# TI_SCH.net
KiCad netlist of a schematic drawn in Altium Designer
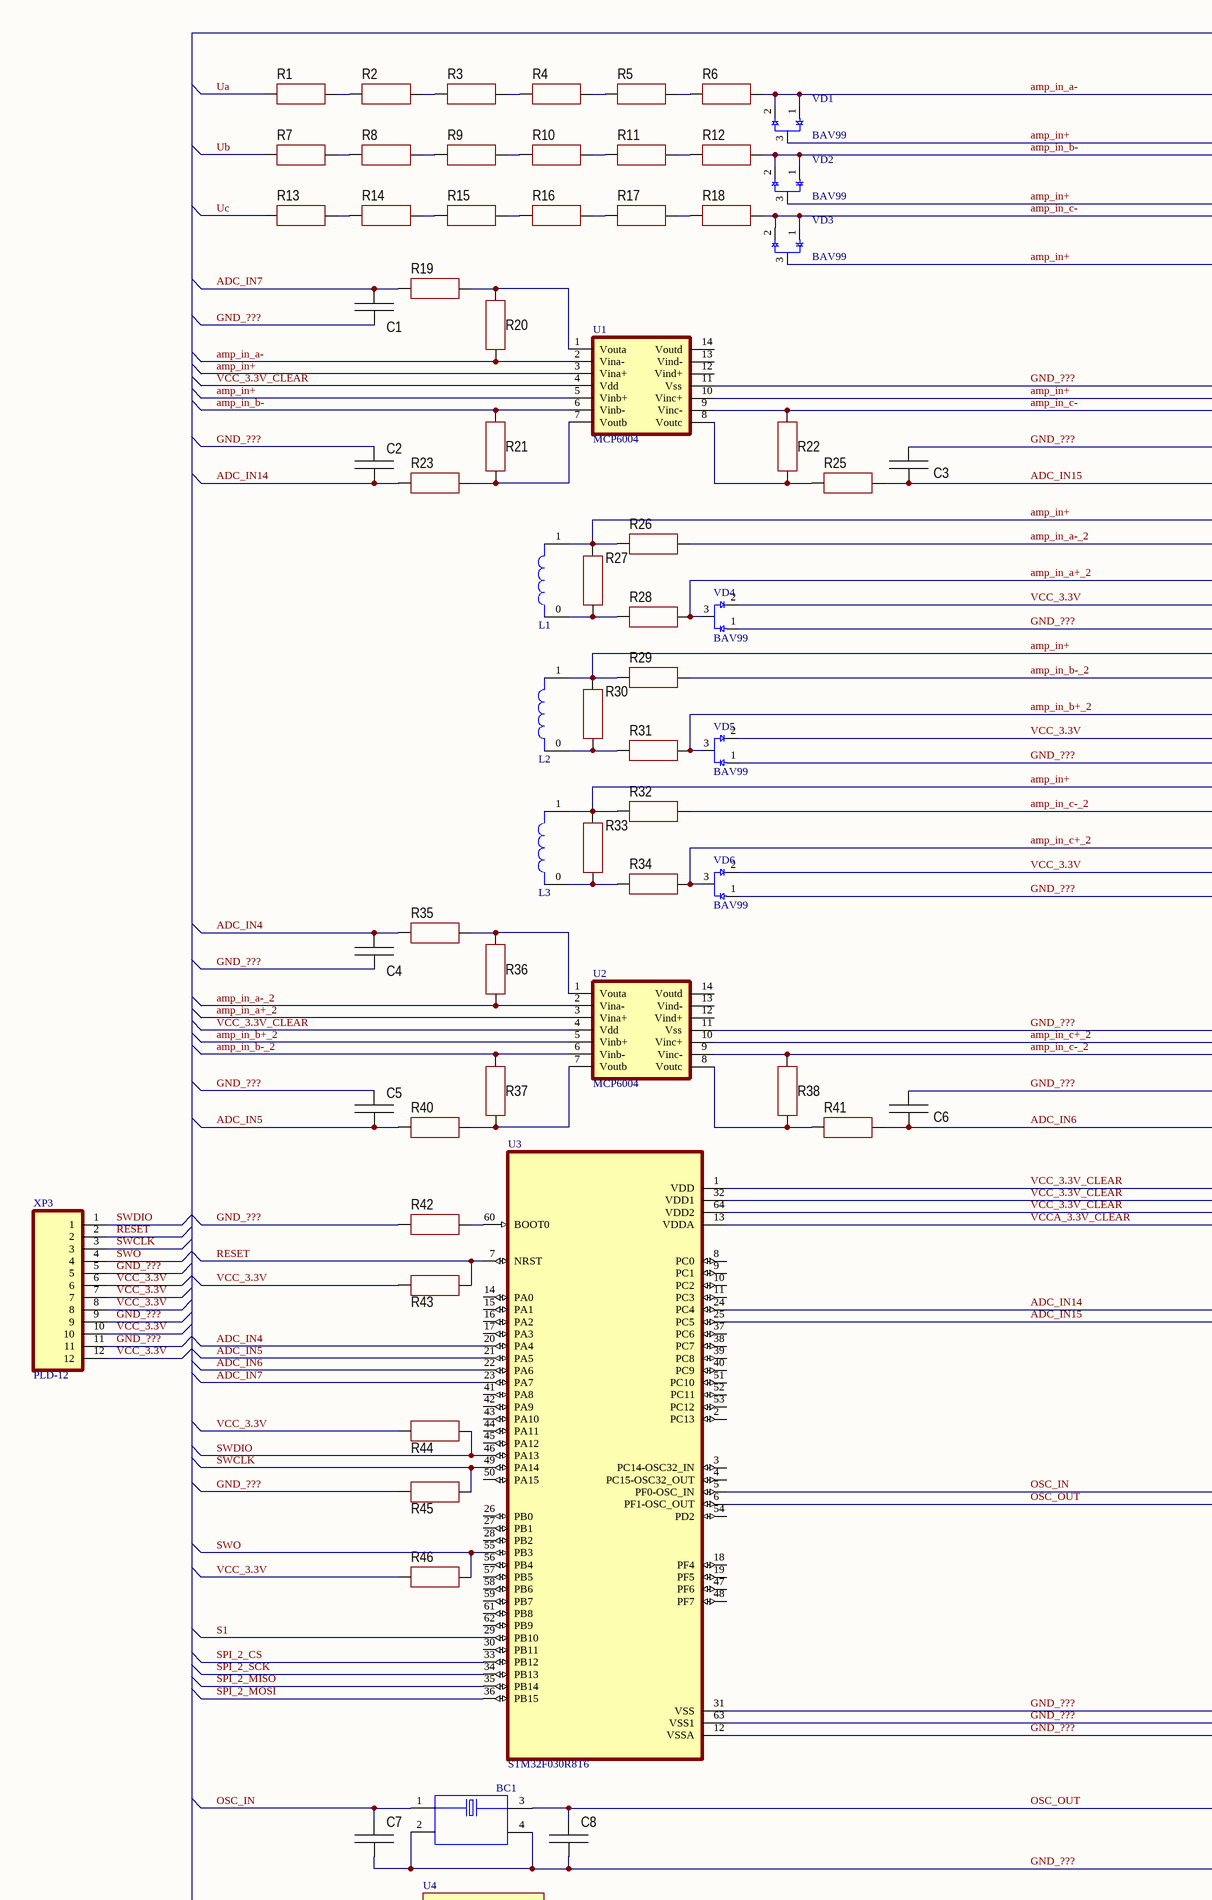
[diagram p0: TI_SCH.SchDoc, row 1 of 4 left]
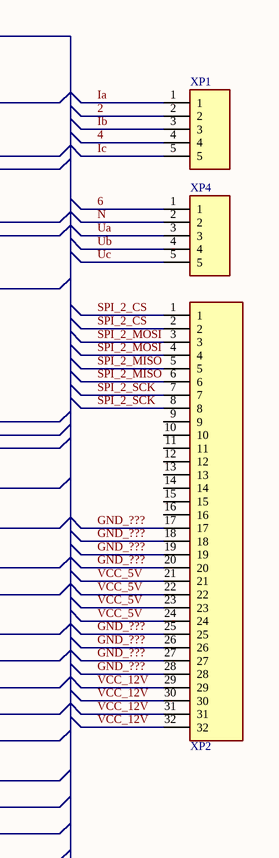
[diagram p1: TI_SCH.SchDoc, row 1 of 4 right]
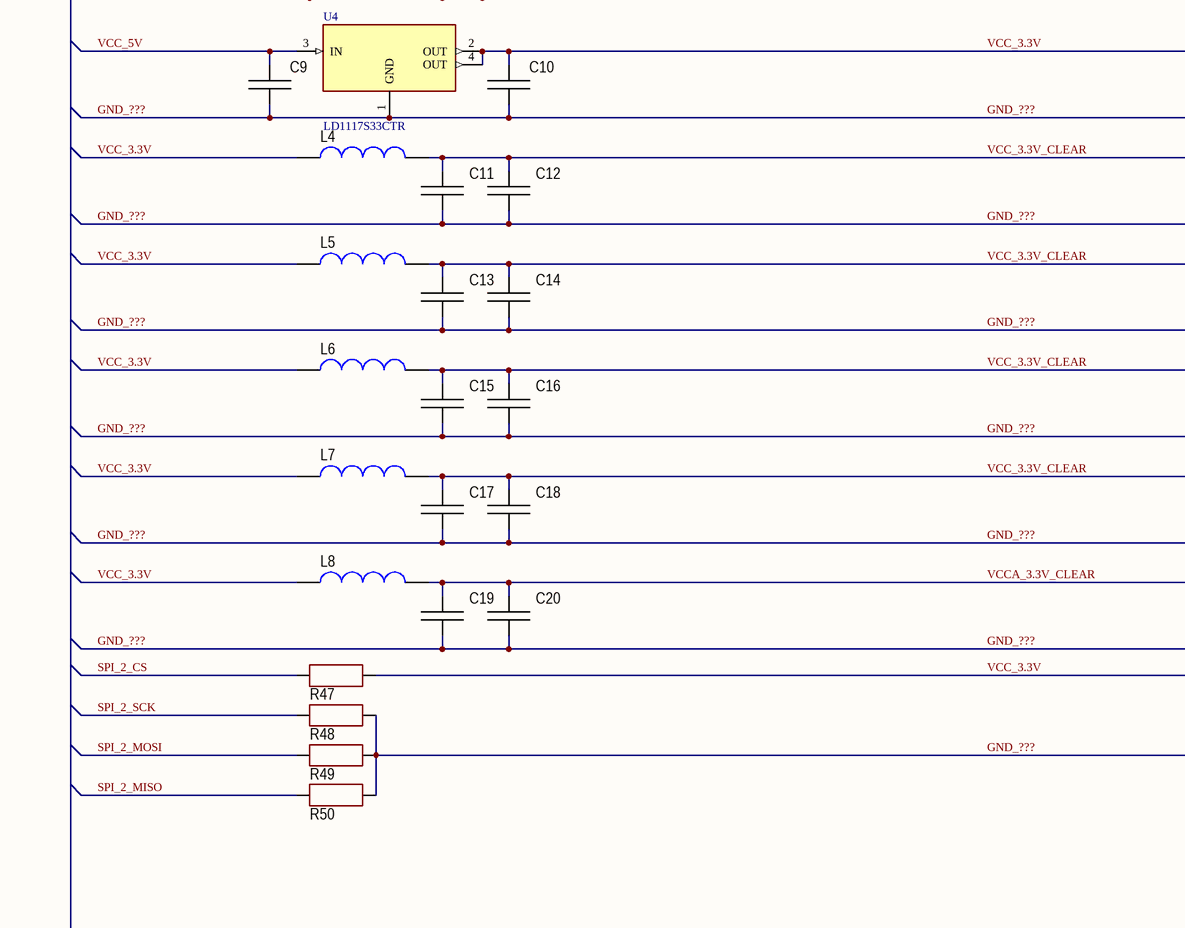
[diagram p2: TI_SCH.SchDoc, row 2 of 4 left]

(export (version "E")
  (design (tool "Eeschema 10.0.6"))
  (components
    (comp (ref "BC1")
      (value "NX2520SA-24.000000MHZ-B8")
      (footprint "XTAL_NX2520SA-24.000000MHZ-B8")
      (description "24MHz Â±10ppm Crystal 10pF 100 Ohms 4-SMD, No Lead")
      (libsource (lib "NX2520") (part "NX2520SA-24.000000MHZ-B8"))
    )
    (comp (ref "C1") (value "~") (footprint "CAP: 0603") (libsource (lib "capacitor") (part "Ceramic_0603")))
    (comp (ref "C2") (value "~") (footprint "CAP: 0603") (libsource (lib "capacitor") (part "Ceramic_0603")))
    (comp (ref "C3") (value "~") (footprint "CAP: 0603") (libsource (lib "capacitor") (part "Ceramic_0603")))
    (comp (ref "C4") (value "~") (footprint "CAP: 0603") (libsource (lib "capacitor") (part "Ceramic_0603")))
    (comp (ref "C5") (value "~") (footprint "CAP: 0603") (libsource (lib "capacitor") (part "Ceramic_0603")))
    (comp (ref "C6") (value "~") (footprint "CAP: 0603") (libsource (lib "capacitor") (part "Ceramic_0603")))
    (comp (ref "C7") (value "~") (footprint "CAP: 0603") (libsource (lib "capacitor") (part "Ceramic_0603")))
    (comp (ref "C8") (value "~") (footprint "CAP: 0603") (libsource (lib "capacitor") (part "Ceramic_0603")))
    (comp (ref "C9") (value "~") (footprint "CAP: 2220") (libsource (lib "capacitor") (part "Ceramic_2220")))
    (comp (ref "C10") (value "~") (footprint "CAP: 2220") (libsource (lib "capacitor") (part "Ceramic_2220")))
    (comp (ref "C11") (value "~") (footprint "CAP: 0603") (libsource (lib "capacitor") (part "Ceramic_0603")))
    (comp (ref "C12") (value "~") (footprint "CAP: 0603") (libsource (lib "capacitor") (part "Ceramic_0603")))
    (comp (ref "C13") (value "~") (footprint "CAP: 0603") (libsource (lib "capacitor") (part "Ceramic_0603")))
    (comp (ref "C14") (value "~") (footprint "CAP: 0603") (libsource (lib "capacitor") (part "Ceramic_0603")))
    (comp (ref "C15") (value "~") (footprint "CAP: 0603") (libsource (lib "capacitor") (part "Ceramic_0603")))
    (comp (ref "C16") (value "~") (footprint "CAP: 0603") (libsource (lib "capacitor") (part "Ceramic_0603")))
    (comp (ref "C17") (value "~") (footprint "CAP: 0603") (libsource (lib "capacitor") (part "Ceramic_0603")))
    (comp (ref "C18") (value "~") (footprint "CAP: 0603") (libsource (lib "capacitor") (part "Ceramic_0603")))
    (comp (ref "C19") (value "~") (footprint "CAP: 0603") (libsource (lib "capacitor") (part "Ceramic_0603")))
    (comp (ref "C20") (value "~") (footprint "CAP: 0603") (libsource (lib "capacitor") (part "Ceramic_0603")))
    (comp (ref "L1") (value "inductor") (footprint "inductor") (libsource (lib "inductor") (part "inductor")))
    (comp (ref "L2") (value "inductor") (footprint "inductor") (libsource (lib "inductor") (part "inductor")))
    (comp (ref "L3") (value "inductor") (footprint "inductor") (libsource (lib "inductor") (part "inductor")))
    (comp (ref "L4") (value "~") (footprint "IND: 0603") (libsource (lib "inductor") (part "Inductor_0603")))
    (comp (ref "L5") (value "~") (footprint "IND: 0603") (libsource (lib "inductor") (part "Inductor_0603")))
    (comp (ref "L6") (value "~") (footprint "IND: 0603") (libsource (lib "inductor") (part "Inductor_0603")))
    (comp (ref "L7") (value "~") (footprint "IND: 0603") (libsource (lib "inductor") (part "Inductor_0603")))
    (comp (ref "L8") (value "~") (footprint "IND: 0603") (libsource (lib "inductor") (part "Inductor_0603")))
    (comp (ref "R1") (value "~") (footprint "RES: 0603") (libsource (lib "resistor") (part "Resistor_0603")))
    (comp (ref "R2") (value "~") (footprint "RES: 0603") (libsource (lib "resistor") (part "Resistor_0603")))
    (comp (ref "R3") (value "~") (footprint "RES: 0603") (libsource (lib "resistor") (part "Resistor_0603")))
    (comp (ref "R4") (value "~") (footprint "RES: 0603") (libsource (lib "resistor") (part "Resistor_0603")))
    (comp (ref "R5") (value "~") (footprint "RES: 0603") (libsource (lib "resistor") (part "Resistor_0603")))
    (comp (ref "R6") (value "~") (footprint "RES: 0603") (libsource (lib "resistor") (part "Resistor_0603")))
    (comp (ref "R7") (value "~") (footprint "RES: 0603") (libsource (lib "resistor") (part "Resistor_0603")))
    (comp (ref "R8") (value "~") (footprint "RES: 0603") (libsource (lib "resistor") (part "Resistor_0603")))
    (comp (ref "R9") (value "~") (footprint "RES: 0603") (libsource (lib "resistor") (part "Resistor_0603")))
    (comp (ref "R10") (value "~") (footprint "RES: 0603") (libsource (lib "resistor") (part "Resistor_0603")))
    (comp (ref "R11") (value "~") (footprint "RES: 0603") (libsource (lib "resistor") (part "Resistor_0603")))
    (comp (ref "R12") (value "~") (footprint "RES: 0603") (libsource (lib "resistor") (part "Resistor_0603")))
    (comp (ref "R13") (value "~") (footprint "RES: 0603") (libsource (lib "resistor") (part "Resistor_0603")))
    (comp (ref "R14") (value "~") (footprint "RES: 0603") (libsource (lib "resistor") (part "Resistor_0603")))
    (comp (ref "R15") (value "~") (footprint "RES: 0603") (libsource (lib "resistor") (part "Resistor_0603")))
    (comp (ref "R16") (value "~") (footprint "RES: 0603") (libsource (lib "resistor") (part "Resistor_0603")))
    (comp (ref "R17") (value "~") (footprint "RES: 0603") (libsource (lib "resistor") (part "Resistor_0603")))
    (comp (ref "R18") (value "~") (footprint "RES: 0603") (libsource (lib "resistor") (part "Resistor_0603")))
    (comp (ref "R19") (value "~") (footprint "RES: 0603") (libsource (lib "resistor") (part "Resistor_0603")))
    (comp (ref "R20") (value "~") (footprint "RES: 0603") (libsource (lib "") (part "Resistor_0603_2")))
    (comp (ref "R21") (value "~") (footprint "RES: 0603") (libsource (lib "") (part "Resistor_0603_2")))
    (comp (ref "R22") (value "~") (footprint "RES: 0603") (libsource (lib "") (part "Resistor_0603_2")))
    (comp (ref "R23") (value "~") (footprint "RES: 0603") (libsource (lib "resistor") (part "Resistor_0603")))
    (comp (ref "R25") (value "~") (footprint "RES: 0603") (libsource (lib "resistor") (part "Resistor_0603")))
    (comp (ref "R26") (value "~") (footprint "RES: 0603") (libsource (lib "resistor") (part "Resistor_0603")))
    (comp (ref "R27") (value "~") (footprint "RES: 0603") (libsource (lib "") (part "Resistor_0603_2")))
    (comp (ref "R28") (value "~") (footprint "RES: 0603") (libsource (lib "resistor") (part "Resistor_0603")))
    (comp (ref "R29") (value "~") (footprint "RES: 0603") (libsource (lib "resistor") (part "Resistor_0603")))
    (comp (ref "R30") (value "~") (footprint "RES: 0603") (libsource (lib "") (part "Resistor_0603_2")))
    (comp (ref "R31") (value "~") (footprint "RES: 0603") (libsource (lib "resistor") (part "Resistor_0603")))
    (comp (ref "R32") (value "~") (footprint "RES: 0603") (libsource (lib "resistor") (part "Resistor_0603")))
    (comp (ref "R33") (value "~") (footprint "RES: 0603") (libsource (lib "") (part "Resistor_0603_2")))
    (comp (ref "R34") (value "~") (footprint "RES: 0603") (libsource (lib "resistor") (part "Resistor_0603")))
    (comp (ref "R35") (value "~") (footprint "RES: 0603") (libsource (lib "resistor") (part "Resistor_0603")))
    (comp (ref "R36") (value "~") (footprint "RES: 0603") (libsource (lib "") (part "Resistor_0603_2")))
    (comp (ref "R37") (value "~") (footprint "RES: 0603") (libsource (lib "") (part "Resistor_0603_2")))
    (comp (ref "R38") (value "~") (footprint "RES: 0603") (libsource (lib "") (part "Resistor_0603_2")))
    (comp (ref "R40") (value "~") (footprint "RES: 0603") (libsource (lib "resistor") (part "Resistor_0603")))
    (comp (ref "R41") (value "~") (footprint "RES: 0603") (libsource (lib "resistor") (part "Resistor_0603")))
    (comp (ref "R42") (value "~") (footprint "RES: 0603") (libsource (lib "resistor") (part "Resistor_0603")))
    (comp (ref "R43") (value "~") (footprint "RES: 0603") (libsource (lib "resistor") (part "Resistor_0603")))
    (comp (ref "R44") (value "~") (footprint "RES: 0603") (libsource (lib "resistor") (part "Resistor_0603")))
    (comp (ref "R45") (value "~") (footprint "RES: 0603") (libsource (lib "resistor") (part "Resistor_0603")))
    (comp (ref "R46") (value "~") (footprint "RES: 0603") (libsource (lib "") (part "Resistor_0603_1")))
    (comp (ref "R47") (value "~") (footprint "RES: 0603") (libsource (lib "") (part "Resistor_0603_1")))
    (comp (ref "R48") (value "~") (footprint "RES: 0603") (libsource (lib "") (part "Resistor_0603_1")))
    (comp (ref "R49") (value "~") (footprint "RES: 0603") (libsource (lib "") (part "Resistor_0603_1")))
    (comp (ref "R50") (value "~") (footprint "RES: 0603") (libsource (lib "") (part "Resistor_0603_1")))
    (comp (ref "U1") (value "MCP6004") (footprint "MCP6004") (libsource (lib "MCP6004") (part "MCP6004")))
    (comp (ref "U2") (value "MCP6004") (footprint "MCP6004") (libsource (lib "MCP6004") (part "MCP6004")))
    (comp (ref "U3")
      (value "STM32F030R8T6")
      (footprint "STM32F030R8T6")
      (libsource (lib "STM32F030R8T6") (part "STM32F030R8T6"))
    )
    (comp (ref "U4")
      (value "LD1117S33CTR")
      (footprint "LD1117S33CTR")
      (description "Linear Voltage Regulator IC 1 Output 800mA SOT-223")
      (libsource (lib "LD1117S33CTR") (part "LD1117S33CTR"))
    )
    (comp (ref "VD1") (value "BAV99") (footprint "BAV99") (libsource (lib "BAV99") (part "BAV99")))
    (comp (ref "VD2") (value "BAV99") (footprint "BAV99") (libsource (lib "BAV99") (part "BAV99")))
    (comp (ref "VD3") (value "BAV99") (footprint "BAV99") (libsource (lib "BAV99") (part "BAV99")))
    (comp (ref "VD4") (value "BAV99") (footprint "BAV99") (libsource (lib "BAV99") (part "BAV99")))
    (comp (ref "VD5") (value "BAV99") (footprint "BAV99") (libsource (lib "BAV99") (part "BAV99")))
    (comp (ref "VD6") (value "BAV99") (footprint "BAV99") (libsource (lib "BAV99") (part "BAV99")))
    (comp (ref "XP1")
      (value "MSTB 2.5 5-GF-5.08")
      (footprint "MSTB 2.5 5-GF-5.08")
      (libsource (lib "MSTB 2,5 5-GF-5,08") (part "MSTB 2,5 5-GF-5,08"))
    )
    (comp (ref "XP2")
      (value "DIN41612R (DS1118-32M-R23)")
      (footprint "DIN41612R (DS1118-32M-R23)")
      (libsource (lib "DIN41612R (DS1118-32M-R23)") (part "DIN41612R (DS1118-32M-R23)"))
    )
    (comp (ref "XP3") (value "PLD-12") (footprint "PLD-12") (libsource (lib "PLD-12") (part "PLD-12")))
    (comp (ref "XP4")
      (value "MSTB 2.5 5-GF-5.08")
      (footprint "MSTB 2.5 5-GF-5.08")
      (libsource (lib "MSTB 2,5 5-GF-5,08") (part "MSTB 2,5 5-GF-5,08"))
    )
  )
  (nets
    (net (code "1") (name "/2") (class "Default")
      (node (ref "XP1") (pin "2") (pinfunction "2_2") (pintype "passive"))
    )
    (net (code "2") (name "/4") (class "Default")
      (node (ref "XP1") (pin "4") (pinfunction "4_4") (pintype "passive"))
    )
    (net (code "3") (name "/6") (class "Default")
      (node (ref "XP4") (pin "1") (pinfunction "1_1") (pintype "passive"))
    )
    (net (code "4") (name "/ADC_IN4") (class "Default")
      (node (ref "C4") (pin "1") (pinfunction "1_1") (pintype "passive"))
      (node (ref "R35") (pin "1") (pinfunction "1_1") (pintype "passive"))
      (node (ref "U3") (pin "20") (pinfunction "PA4_20") (pintype "bidirectional"))
    )
    (net (code "5") (name "/ADC_IN5") (class "Default")
      (node (ref "C5") (pin "1") (pinfunction "1_1") (pintype "passive"))
      (node (ref "R40") (pin "1") (pinfunction "1_1") (pintype "passive"))
      (node (ref "U3") (pin "21") (pinfunction "PA5_21") (pintype "bidirectional"))
    )
    (net (code "6") (name "/ADC_IN6") (class "Default")
      (node (ref "C6") (pin "1") (pinfunction "1_1") (pintype "passive"))
      (node (ref "R41") (pin "2") (pinfunction "2_2") (pintype "passive"))
      (node (ref "U3") (pin "22") (pinfunction "PA6_22") (pintype "bidirectional"))
    )
    (net (code "7") (name "/ADC_IN7") (class "Default")
      (node (ref "C1") (pin "1") (pinfunction "1_1") (pintype "passive"))
      (node (ref "R19") (pin "1") (pinfunction "1_1") (pintype "passive"))
      (node (ref "U3") (pin "23") (pinfunction "PA7_23") (pintype "bidirectional"))
    )
    (net (code "8") (name "/ADC_IN14") (class "Default")
      (node (ref "C2") (pin "1") (pinfunction "1_1") (pintype "passive"))
      (node (ref "R23") (pin "1") (pinfunction "1_1") (pintype "passive"))
      (node (ref "U3") (pin "24") (pinfunction "PC4_24") (pintype "bidirectional"))
    )
    (net (code "9") (name "/ADC_IN15") (class "Default")
      (node (ref "C3") (pin "1") (pinfunction "1_1") (pintype "passive"))
      (node (ref "R25") (pin "2") (pinfunction "2_2") (pintype "passive"))
      (node (ref "U3") (pin "25") (pinfunction "PC5_25") (pintype "bidirectional"))
    )
    (net (code "10") (name "/GND_???") (class "Default")
      (node (ref "BC1") (pin "2") (pinfunction "2_2") (pintype "passive"))
      (node (ref "BC1") (pin "4") (pinfunction "4_4") (pintype "passive"))
      (node (ref "C1") (pin "2") (pinfunction "2_2") (pintype "passive"))
      (node (ref "C10") (pin "1") (pinfunction "1_1") (pintype "passive"))
      (node (ref "C11") (pin "1") (pinfunction "1_1") (pintype "passive"))
      (node (ref "C12") (pin "1") (pinfunction "1_1") (pintype "passive"))
      (node (ref "C13") (pin "1") (pinfunction "1_1") (pintype "passive"))
      (node (ref "C14") (pin "1") (pinfunction "1_1") (pintype "passive"))
      (node (ref "C15") (pin "1") (pinfunction "1_1") (pintype "passive"))
      (node (ref "C16") (pin "1") (pinfunction "1_1") (pintype "passive"))
      (node (ref "C17") (pin "1") (pinfunction "1_1") (pintype "passive"))
      (node (ref "C18") (pin "1") (pinfunction "1_1") (pintype "passive"))
      (node (ref "C19") (pin "1") (pinfunction "1_1") (pintype "passive"))
      (node (ref "C2") (pin "2") (pinfunction "2_2") (pintype "passive"))
      (node (ref "C20") (pin "1") (pinfunction "1_1") (pintype "passive"))
      (node (ref "C3") (pin "2") (pinfunction "2_2") (pintype "passive"))
      (node (ref "C4") (pin "2") (pinfunction "2_2") (pintype "passive"))
      (node (ref "C5") (pin "2") (pinfunction "2_2") (pintype "passive"))
      (node (ref "C6") (pin "2") (pinfunction "2_2") (pintype "passive"))
      (node (ref "C7") (pin "2") (pinfunction "2_2") (pintype "passive"))
      (node (ref "C8") (pin "2") (pinfunction "2_2") (pintype "passive"))
      (node (ref "C9") (pin "1") (pinfunction "1_1") (pintype "passive"))
      (node (ref "R42") (pin "1") (pinfunction "1_1") (pintype "passive"))
      (node (ref "R45") (pin "1") (pinfunction "1_1") (pintype "passive"))
      (node (ref "R48") (pin "1") (pinfunction "1_1") (pintype "passive"))
      (node (ref "R49") (pin "1") (pinfunction "1_1") (pintype "passive"))
      (node (ref "R50") (pin "1") (pinfunction "1_1") (pintype "passive"))
      (node (ref "U1") (pin "11") (pinfunction "Vss_11") (pintype "power_in"))
      (node (ref "U2") (pin "11") (pinfunction "Vss_11") (pintype "power_in"))
      (node (ref "U3") (pin "12") (pinfunction "VSSA_12") (pintype "power_in"))
      (node (ref "U3") (pin "31") (pinfunction "VSS_31") (pintype "power_in"))
      (node (ref "U3") (pin "63") (pinfunction "VSS1_63") (pintype "power_in"))
      (node (ref "U4") (pin "1") (pinfunction "GND_1") (pintype "passive"))
      (node (ref "VD4") (pin "1") (pinfunction "G_1") (pintype "passive"))
      (node (ref "VD5") (pin "1") (pinfunction "G_1") (pintype "passive"))
      (node (ref "VD6") (pin "1") (pinfunction "G_1") (pintype "passive"))
      (node (ref "XP2") (pin "17") (pinfunction "17_17") (pintype "passive"))
      (node (ref "XP2") (pin "18") (pinfunction "18_18") (pintype "passive"))
      (node (ref "XP2") (pin "19") (pinfunction "19_19") (pintype "passive"))
      (node (ref "XP2") (pin "20") (pinfunction "20_20") (pintype "passive"))
      (node (ref "XP2") (pin "25") (pinfunction "25_25") (pintype "passive"))
      (node (ref "XP2") (pin "26") (pinfunction "26_26") (pintype "passive"))
      (node (ref "XP2") (pin "27") (pinfunction "27_27") (pintype "passive"))
      (node (ref "XP2") (pin "28") (pinfunction "28_28") (pintype "passive"))
      (node (ref "XP3") (pin "11") (pinfunction "11_11") (pintype "passive"))
      (node (ref "XP3") (pin "5") (pinfunction "5_5") (pintype "passive"))
      (node (ref "XP3") (pin "9") (pinfunction "9_9") (pintype "passive"))
    )
    (net (code "11") (name "/Ia") (class "Default")
      (node (ref "XP1") (pin "1") (pinfunction "1_1") (pintype "passive"))
    )
    (net (code "12") (name "/Ib") (class "Default")
      (node (ref "XP1") (pin "3") (pinfunction "3_3") (pintype "passive"))
    )
    (net (code "13") (name "/Ic") (class "Default")
      (node (ref "XP1") (pin "5") (pinfunction "5_5") (pintype "passive"))
    )
    (net (code "14") (name "/N") (class "Default")
      (node (ref "XP4") (pin "2") (pinfunction "2_2") (pintype "passive"))
    )
    (net (code "15") (name "/OSC_IN") (class "Default")
      (node (ref "BC1") (pin "1") (pinfunction "1_1") (pintype "passive"))
      (node (ref "C7") (pin "1") (pinfunction "1_1") (pintype "passive"))
      (node (ref "U3") (pin "5") (pinfunction "PF0-OSC_IN_5") (pintype "bidirectional"))
    )
    (net (code "16") (name "/OSC_OUT") (class "Default")
      (node (ref "BC1") (pin "3") (pinfunction "3_3") (pintype "passive"))
      (node (ref "C8") (pin "1") (pinfunction "1_1") (pintype "passive"))
      (node (ref "U3") (pin "6") (pinfunction "PF1-OSC_OUT_6") (pintype "bidirectional"))
    )
    (net (code "17") (name "/RESET") (class "Default")
      (node (ref "R43") (pin "2") (pinfunction "2_2") (pintype "passive"))
      (node (ref "U3") (pin "7") (pinfunction "NRST_7") (pintype "bidirectional"))
      (node (ref "XP3") (pin "2") (pinfunction "2_2") (pintype "passive"))
    )
    (net (code "18") (name "/S1") (class "Default")
      (node (ref "U3") (pin "29") (pinfunction "PB10_29") (pintype "bidirectional"))
    )
    (net (code "19") (name "/SPI_2_CS") (class "Default")
      (node (ref "R47") (pin "2") (pinfunction "2_2") (pintype "passive"))
      (node (ref "U3") (pin "33") (pinfunction "PB12_33") (pintype "bidirectional"))
      (node (ref "XP2") (pin "1") (pinfunction "1_1") (pintype "passive"))
      (node (ref "XP2") (pin "2") (pinfunction "2_2") (pintype "passive"))
    )
    (net (code "20") (name "/SPI_2_MISO") (class "Default")
      (node (ref "R50") (pin "2") (pinfunction "2_2") (pintype "passive"))
      (node (ref "U3") (pin "35") (pinfunction "PB14_35") (pintype "bidirectional"))
      (node (ref "XP2") (pin "5") (pinfunction "5_5") (pintype "passive"))
      (node (ref "XP2") (pin "6") (pinfunction "6_6") (pintype "passive"))
    )
    (net (code "21") (name "/SPI_2_MOSI") (class "Default")
      (node (ref "R49") (pin "2") (pinfunction "2_2") (pintype "passive"))
      (node (ref "U3") (pin "36") (pinfunction "PB15_36") (pintype "bidirectional"))
      (node (ref "XP2") (pin "3") (pinfunction "3_3") (pintype "passive"))
      (node (ref "XP2") (pin "4") (pinfunction "4_4") (pintype "passive"))
    )
    (net (code "22") (name "/SPI_2_SCK") (class "Default")
      (node (ref "R48") (pin "2") (pinfunction "2_2") (pintype "passive"))
      (node (ref "U3") (pin "34") (pinfunction "PB13_34") (pintype "bidirectional"))
      (node (ref "XP2") (pin "7") (pinfunction "7_7") (pintype "passive"))
      (node (ref "XP2") (pin "8") (pinfunction "8_8") (pintype "passive"))
    )
    (net (code "23") (name "/SWCLK") (class "Default")
      (node (ref "R45") (pin "2") (pinfunction "2_2") (pintype "passive"))
      (node (ref "U3") (pin "49") (pinfunction "PA14_49") (pintype "bidirectional"))
      (node (ref "XP3") (pin "3") (pinfunction "3_3") (pintype "passive"))
    )
    (net (code "24") (name "/SWDIO") (class "Default")
      (node (ref "R44") (pin "2") (pinfunction "2_2") (pintype "passive"))
      (node (ref "U3") (pin "46") (pinfunction "PA13_46") (pintype "bidirectional"))
      (node (ref "XP3") (pin "1") (pinfunction "1_1") (pintype "passive"))
    )
    (net (code "25") (name "/SWO") (class "Default")
      (node (ref "R46") (pin "1") (pinfunction "1_1") (pintype "passive"))
      (node (ref "U3") (pin "55") (pinfunction "PB3_55") (pintype "bidirectional"))
      (node (ref "XP3") (pin "4") (pinfunction "4_4") (pintype "passive"))
    )
    (net (code "26") (name "/Ua") (class "Default")
      (node (ref "R1") (pin "1") (pinfunction "1_1") (pintype "passive"))
      (node (ref "XP4") (pin "3") (pinfunction "3_3") (pintype "passive"))
    )
    (net (code "27") (name "/Ub") (class "Default")
      (node (ref "R7") (pin "1") (pinfunction "1_1") (pintype "passive"))
      (node (ref "XP4") (pin "4") (pinfunction "4_4") (pintype "passive"))
    )
    (net (code "28") (name "/Uc") (class "Default")
      (node (ref "R13") (pin "1") (pinfunction "1_1") (pintype "passive"))
      (node (ref "XP4") (pin "5") (pinfunction "5_5") (pintype "passive"))
    )
    (net (code "29") (name "/VCCA_3.3V_CLEAR") (class "Default")
      (node (ref "C19") (pin "2") (pinfunction "2_2") (pintype "passive"))
      (node (ref "C20") (pin "2") (pinfunction "2_2") (pintype "passive"))
      (node (ref "L8") (pin "1") (pinfunction "1_1") (pintype "passive"))
      (node (ref "U3") (pin "13") (pinfunction "VDDA_13") (pintype "power_in"))
    )
    (net (code "30") (name "/VCC_3.3V") (class "Default")
      (node (ref "C10") (pin "2") (pinfunction "2_2") (pintype "passive"))
      (node (ref "L4") (pin "2") (pinfunction "2_2") (pintype "passive"))
      (node (ref "L5") (pin "2") (pinfunction "2_2") (pintype "passive"))
      (node (ref "L6") (pin "2") (pinfunction "2_2") (pintype "passive"))
      (node (ref "L7") (pin "2") (pinfunction "2_2") (pintype "passive"))
      (node (ref "L8") (pin "2") (pinfunction "2_2") (pintype "passive"))
      (node (ref "R43") (pin "1") (pinfunction "1_1") (pintype "passive"))
      (node (ref "R44") (pin "1") (pinfunction "1_1") (pintype "passive"))
      (node (ref "R46") (pin "2") (pinfunction "2_2") (pintype "passive"))
      (node (ref "R47") (pin "1") (pinfunction "1_1") (pintype "passive"))
      (node (ref "U4") (pin "2") (pinfunction "OUT_2") (pintype "output"))
      (node (ref "U4") (pin "4") (pinfunction "OUT_4") (pintype "output"))
      (node (ref "VD4") (pin "2") (pinfunction "S_2") (pintype "passive"))
      (node (ref "VD5") (pin "2") (pinfunction "S_2") (pintype "passive"))
      (node (ref "VD6") (pin "2") (pinfunction "S_2") (pintype "passive"))
      (node (ref "XP3") (pin "10") (pinfunction "10_10") (pintype "passive"))
      (node (ref "XP3") (pin "12") (pinfunction "12_12") (pintype "passive"))
      (node (ref "XP3") (pin "6") (pinfunction "6_6") (pintype "passive"))
      (node (ref "XP3") (pin "7") (pinfunction "7_7") (pintype "passive"))
      (node (ref "XP3") (pin "8") (pinfunction "8_8") (pintype "passive"))
    )
    (net (code "31") (name "/VCC_3.3V_CLEAR") (class "Default")
      (node (ref "C11") (pin "2") (pinfunction "2_2") (pintype "passive"))
      (node (ref "C12") (pin "2") (pinfunction "2_2") (pintype "passive"))
      (node (ref "C13") (pin "2") (pinfunction "2_2") (pintype "passive"))
      (node (ref "C14") (pin "2") (pinfunction "2_2") (pintype "passive"))
      (node (ref "C15") (pin "2") (pinfunction "2_2") (pintype "passive"))
      (node (ref "C16") (pin "2") (pinfunction "2_2") (pintype "passive"))
      (node (ref "C17") (pin "2") (pinfunction "2_2") (pintype "passive"))
      (node (ref "C18") (pin "2") (pinfunction "2_2") (pintype "passive"))
      (node (ref "L4") (pin "1") (pinfunction "1_1") (pintype "passive"))
      (node (ref "L5") (pin "1") (pinfunction "1_1") (pintype "passive"))
      (node (ref "L6") (pin "1") (pinfunction "1_1") (pintype "passive"))
      (node (ref "L7") (pin "1") (pinfunction "1_1") (pintype "passive"))
      (node (ref "U1") (pin "4") (pinfunction "Vdd_4") (pintype "power_in"))
      (node (ref "U2") (pin "4") (pinfunction "Vdd_4") (pintype "power_in"))
      (node (ref "U3") (pin "1") (pinfunction "VDD_1") (pintype "power_in"))
      (node (ref "U3") (pin "32") (pinfunction "VDD1_32") (pintype "power_in"))
      (node (ref "U3") (pin "64") (pinfunction "VDD2_64") (pintype "power_in"))
    )
    (net (code "32") (name "/VCC_5V") (class "Default")
      (node (ref "C9") (pin "2") (pinfunction "2_2") (pintype "passive"))
      (node (ref "U4") (pin "3") (pinfunction "IN_3") (pintype "input"))
      (node (ref "XP2") (pin "21") (pinfunction "21_21") (pintype "passive"))
      (node (ref "XP2") (pin "22") (pinfunction "22_22") (pintype "passive"))
      (node (ref "XP2") (pin "23") (pinfunction "23_23") (pintype "passive"))
      (node (ref "XP2") (pin "24") (pinfunction "24_24") (pintype "passive"))
    )
    (net (code "33") (name "/VCC_12V") (class "Default")
      (node (ref "XP2") (pin "29") (pinfunction "29_29") (pintype "passive"))
      (node (ref "XP2") (pin "30") (pinfunction "30_30") (pintype "passive"))
      (node (ref "XP2") (pin "31") (pinfunction "31_31") (pintype "passive"))
      (node (ref "XP2") (pin "32") (pinfunction "32_32") (pintype "passive"))
    )
    (net (code "34") (name "/amp_in+") (class "Default")
      (node (ref "L1") (pin "1") (pinfunction "1_1") (pintype "power_in"))
      (node (ref "L2") (pin "1") (pinfunction "1_1") (pintype "power_in"))
      (node (ref "L3") (pin "1") (pinfunction "1_1") (pintype "power_in"))
      (node (ref "R26") (pin "1") (pinfunction "1_1") (pintype "passive"))
      (node (ref "R27") (pin "2") (pinfunction "2_2") (pintype "passive"))
      (node (ref "R29") (pin "1") (pinfunction "1_1") (pintype "passive"))
      (node (ref "R30") (pin "2") (pinfunction "2_2") (pintype "passive"))
      (node (ref "R32") (pin "1") (pinfunction "1_1") (pintype "passive"))
      (node (ref "R33") (pin "2") (pinfunction "2_2") (pintype "passive"))
      (node (ref "U1") (pin "10") (pinfunction "Vinc+_10") (pintype "power_in"))
      (node (ref "U1") (pin "3") (pinfunction "Vina+_3") (pintype "power_in"))
      (node (ref "U1") (pin "5") (pinfunction "Vinb+_5") (pintype "power_in"))
      (node (ref "VD1") (pin "3") (pinfunction "D_3") (pintype "passive"))
      (node (ref "VD2") (pin "3") (pinfunction "D_3") (pintype "passive"))
      (node (ref "VD3") (pin "3") (pinfunction "D_3") (pintype "passive"))
    )
    (net (code "35") (name "/amp_in_a+_2") (class "Default")
      (node (ref "R28") (pin "2") (pinfunction "2_2") (pintype "passive"))
      (node (ref "U2") (pin "3") (pinfunction "Vina+_3") (pintype "power_in"))
      (node (ref "VD4") (pin "3") (pinfunction "D_3") (pintype "passive"))
    )
    (net (code "36") (name "/amp_in_a-") (class "Default")
      (node (ref "R20") (pin "1") (pinfunction "1_1") (pintype "passive"))
      (node (ref "R6") (pin "2") (pinfunction "2_2") (pintype "passive"))
      (node (ref "U1") (pin "2") (pinfunction "Vina-_2") (pintype "power_in"))
      (node (ref "VD1") (pin "1") (pinfunction "G_1") (pintype "passive"))
      (node (ref "VD1") (pin "2") (pinfunction "S_2") (pintype "passive"))
    )
    (net (code "37") (name "/amp_in_a-_2") (class "Default")
      (node (ref "R26") (pin "2") (pinfunction "2_2") (pintype "passive"))
      (node (ref "R36") (pin "1") (pinfunction "1_1") (pintype "passive"))
      (node (ref "U2") (pin "2") (pinfunction "Vina-_2") (pintype "power_in"))
    )
    (net (code "38") (name "/amp_in_b+_2") (class "Default")
      (node (ref "R31") (pin "2") (pinfunction "2_2") (pintype "passive"))
      (node (ref "U2") (pin "5") (pinfunction "Vinb+_5") (pintype "power_in"))
      (node (ref "VD5") (pin "3") (pinfunction "D_3") (pintype "passive"))
    )
    (net (code "39") (name "/amp_in_b-") (class "Default")
      (node (ref "R12") (pin "2") (pinfunction "2_2") (pintype "passive"))
      (node (ref "R21") (pin "2") (pinfunction "2_2") (pintype "passive"))
      (node (ref "U1") (pin "6") (pinfunction "Vinb-_6") (pintype "power_in"))
      (node (ref "VD2") (pin "1") (pinfunction "G_1") (pintype "passive"))
      (node (ref "VD2") (pin "2") (pinfunction "S_2") (pintype "passive"))
    )
    (net (code "40") (name "/amp_in_b-_2") (class "Default")
      (node (ref "R29") (pin "2") (pinfunction "2_2") (pintype "passive"))
      (node (ref "R37") (pin "2") (pinfunction "2_2") (pintype "passive"))
      (node (ref "U2") (pin "6") (pinfunction "Vinb-_6") (pintype "power_in"))
    )
    (net (code "41") (name "/amp_in_c+_2") (class "Default")
      (node (ref "R34") (pin "2") (pinfunction "2_2") (pintype "passive"))
      (node (ref "U2") (pin "10") (pinfunction "Vinc+_10") (pintype "power_in"))
      (node (ref "VD6") (pin "3") (pinfunction "D_3") (pintype "passive"))
    )
    (net (code "42") (name "/amp_in_c-") (class "Default")
      (node (ref "R18") (pin "2") (pinfunction "2_2") (pintype "passive"))
      (node (ref "R22") (pin "2") (pinfunction "2_2") (pintype "passive"))
      (node (ref "U1") (pin "9") (pinfunction "Vinc-_9") (pintype "power_in"))
      (node (ref "VD3") (pin "1") (pinfunction "G_1") (pintype "passive"))
      (node (ref "VD3") (pin "2") (pinfunction "S_2") (pintype "passive"))
    )
    (net (code "43") (name "/amp_in_c-_2") (class "Default")
      (node (ref "R32") (pin "2") (pinfunction "2_2") (pintype "passive"))
      (node (ref "R38") (pin "2") (pinfunction "2_2") (pintype "passive"))
      (node (ref "U2") (pin "9") (pinfunction "Vinc-_9") (pintype "power_in"))
    )
    (net (code "44") (name "Net-(L1-Pad0)") (class "Default")
      (node (ref "L1") (pin "0") (pinfunction "0_0") (pintype "power_in"))
      (node (ref "R27") (pin "1") (pinfunction "1_1") (pintype "passive"))
      (node (ref "R28") (pin "1") (pinfunction "1_1") (pintype "passive"))
    )
    (net (code "45") (name "Net-(L2-Pad0)") (class "Default")
      (node (ref "L2") (pin "0") (pinfunction "0_0") (pintype "power_in"))
      (node (ref "R30") (pin "1") (pinfunction "1_1") (pintype "passive"))
      (node (ref "R31") (pin "1") (pinfunction "1_1") (pintype "passive"))
    )
    (net (code "46") (name "Net-(L3-Pad0)") (class "Default")
      (node (ref "L3") (pin "0") (pinfunction "0_0") (pintype "power_in"))
      (node (ref "R33") (pin "1") (pinfunction "1_1") (pintype "passive"))
      (node (ref "R34") (pin "1") (pinfunction "1_1") (pintype "passive"))
    )
    (net (code "47") (name "Net-(R1-Pad2)") (class "Default")
      (node (ref "R1") (pin "2") (pinfunction "2_2") (pintype "passive"))
      (node (ref "R2") (pin "1") (pinfunction "1_1") (pintype "passive"))
    )
    (net (code "48") (name "Net-(R2-Pad2)") (class "Default")
      (node (ref "R2") (pin "2") (pinfunction "2_2") (pintype "passive"))
      (node (ref "R3") (pin "1") (pinfunction "1_1") (pintype "passive"))
    )
    (net (code "49") (name "Net-(R3-Pad2)") (class "Default")
      (node (ref "R3") (pin "2") (pinfunction "2_2") (pintype "passive"))
      (node (ref "R4") (pin "1") (pinfunction "1_1") (pintype "passive"))
    )
    (net (code "50") (name "Net-(R4-Pad2)") (class "Default")
      (node (ref "R4") (pin "2") (pinfunction "2_2") (pintype "passive"))
      (node (ref "R5") (pin "1") (pinfunction "1_1") (pintype "passive"))
    )
    (net (code "51") (name "Net-(R5-Pad2)") (class "Default")
      (node (ref "R5") (pin "2") (pinfunction "2_2") (pintype "passive"))
      (node (ref "R6") (pin "1") (pinfunction "1_1") (pintype "passive"))
    )
    (net (code "52") (name "Net-(R7-Pad2)") (class "Default")
      (node (ref "R7") (pin "2") (pinfunction "2_2") (pintype "passive"))
      (node (ref "R8") (pin "1") (pinfunction "1_1") (pintype "passive"))
    )
    (net (code "53") (name "Net-(R8-Pad2)") (class "Default")
      (node (ref "R8") (pin "2") (pinfunction "2_2") (pintype "passive"))
      (node (ref "R9") (pin "1") (pinfunction "1_1") (pintype "passive"))
    )
    (net (code "54") (name "Net-(R10-Pad1)") (class "Default")
      (node (ref "R10") (pin "1") (pinfunction "1_1") (pintype "passive"))
      (node (ref "R9") (pin "2") (pinfunction "2_2") (pintype "passive"))
    )
    (net (code "55") (name "Net-(R10-Pad2)") (class "Default")
      (node (ref "R10") (pin "2") (pinfunction "2_2") (pintype "passive"))
      (node (ref "R11") (pin "1") (pinfunction "1_1") (pintype "passive"))
    )
    (net (code "56") (name "Net-(R11-Pad2)") (class "Default")
      (node (ref "R11") (pin "2") (pinfunction "2_2") (pintype "passive"))
      (node (ref "R12") (pin "1") (pinfunction "1_1") (pintype "passive"))
    )
    (net (code "57") (name "Net-(R13-Pad2)") (class "Default")
      (node (ref "R13") (pin "2") (pinfunction "2_2") (pintype "passive"))
      (node (ref "R14") (pin "1") (pinfunction "1_1") (pintype "passive"))
    )
    (net (code "58") (name "Net-(R14-Pad2)") (class "Default")
      (node (ref "R14") (pin "2") (pinfunction "2_2") (pintype "passive"))
      (node (ref "R15") (pin "1") (pinfunction "1_1") (pintype "passive"))
    )
    (net (code "59") (name "Net-(R15-Pad2)") (class "Default")
      (node (ref "R15") (pin "2") (pinfunction "2_2") (pintype "passive"))
      (node (ref "R16") (pin "1") (pinfunction "1_1") (pintype "passive"))
    )
    (net (code "60") (name "Net-(R16-Pad2)") (class "Default")
      (node (ref "R16") (pin "2") (pinfunction "2_2") (pintype "passive"))
      (node (ref "R17") (pin "1") (pinfunction "1_1") (pintype "passive"))
    )
    (net (code "61") (name "Net-(R17-Pad2)") (class "Default")
      (node (ref "R17") (pin "2") (pinfunction "2_2") (pintype "passive"))
      (node (ref "R18") (pin "1") (pinfunction "1_1") (pintype "passive"))
    )
    (net (code "62") (name "Net-(U1-Vouta)") (class "Default")
      (node (ref "R19") (pin "2") (pinfunction "2_2") (pintype "passive"))
      (node (ref "R20") (pin "2") (pinfunction "2_2") (pintype "passive"))
      (node (ref "U1") (pin "1") (pinfunction "Vouta_1") (pintype "power_in"))
    )
    (net (code "63") (name "Net-(U1-Voutb)") (class "Default")
      (node (ref "R21") (pin "1") (pinfunction "1_1") (pintype "passive"))
      (node (ref "R23") (pin "2") (pinfunction "2_2") (pintype "passive"))
      (node (ref "U1") (pin "7") (pinfunction "Voutb_7") (pintype "power_in"))
    )
    (net (code "64") (name "Net-(U1-Voutc)") (class "Default")
      (node (ref "R22") (pin "1") (pinfunction "1_1") (pintype "passive"))
      (node (ref "R25") (pin "1") (pinfunction "1_1") (pintype "passive"))
      (node (ref "U1") (pin "8") (pinfunction "Voutc_8") (pintype "power_in"))
    )
    (net (code "65") (name "Net-(U2-Vouta)") (class "Default")
      (node (ref "R35") (pin "2") (pinfunction "2_2") (pintype "passive"))
      (node (ref "R36") (pin "2") (pinfunction "2_2") (pintype "passive"))
      (node (ref "U2") (pin "1") (pinfunction "Vouta_1") (pintype "power_in"))
    )
    (net (code "66") (name "Net-(U2-Voutb)") (class "Default")
      (node (ref "R37") (pin "1") (pinfunction "1_1") (pintype "passive"))
      (node (ref "R40") (pin "2") (pinfunction "2_2") (pintype "passive"))
      (node (ref "U2") (pin "7") (pinfunction "Voutb_7") (pintype "power_in"))
    )
    (net (code "67") (name "Net-(U2-Voutc)") (class "Default")
      (node (ref "R38") (pin "1") (pinfunction "1_1") (pintype "passive"))
      (node (ref "R41") (pin "1") (pinfunction "1_1") (pintype "passive"))
      (node (ref "U2") (pin "8") (pinfunction "Voutc_8") (pintype "power_in"))
    )
    (net (code "68") (name "Net-(U3-BOOT0)") (class "Default")
      (node (ref "R42") (pin "2") (pinfunction "2_2") (pintype "passive"))
      (node (ref "U3") (pin "60") (pinfunction "BOOT0_60") (pintype "input"))
    )
    (net (code "69") (name "unconnected-(U1-Vind+-Pad12)") (class "Default")
      (node (ref "U1") (pin "12") (pinfunction "Vind+_12") (pintype "power_in"))
    )
    (net (code "70") (name "unconnected-(U1-Vind--Pad13)") (class "Default")
      (node (ref "U1") (pin "13") (pinfunction "Vind-_13") (pintype "power_in"))
    )
    (net (code "71") (name "unconnected-(U1-Voutd-Pad14)") (class "Default")
      (node (ref "U1") (pin "14") (pinfunction "Voutd_14") (pintype "power_in"))
    )
    (net (code "72") (name "unconnected-(U2-Vind+-Pad12)") (class "Default")
      (node (ref "U2") (pin "12") (pinfunction "Vind+_12") (pintype "power_in"))
    )
    (net (code "73") (name "unconnected-(U2-Vind--Pad13)") (class "Default")
      (node (ref "U2") (pin "13") (pinfunction "Vind-_13") (pintype "power_in"))
    )
    (net (code "74") (name "unconnected-(U2-Voutd-Pad14)") (class "Default")
      (node (ref "U2") (pin "14") (pinfunction "Voutd_14") (pintype "power_in"))
    )
    (net (code "75") (name "unconnected-(U3-PA0-Pad14)") (class "Default")
      (node (ref "U3") (pin "14") (pinfunction "PA0_14") (pintype "bidirectional"))
    )
    (net (code "76") (name "unconnected-(U3-PA1-Pad15)") (class "Default")
      (node (ref "U3") (pin "15") (pinfunction "PA1_15") (pintype "bidirectional"))
    )
    (net (code "77") (name "unconnected-(U3-PA2-Pad16)") (class "Default")
      (node (ref "U3") (pin "16") (pinfunction "PA2_16") (pintype "bidirectional"))
    )
    (net (code "78") (name "unconnected-(U3-PA3-Pad17)") (class "Default")
      (node (ref "U3") (pin "17") (pinfunction "PA3_17") (pintype "bidirectional"))
    )
    (net (code "79") (name "unconnected-(U3-PA8-Pad41)") (class "Default")
      (node (ref "U3") (pin "41") (pinfunction "PA8_41") (pintype "bidirectional"))
    )
    (net (code "80") (name "unconnected-(U3-PA9-Pad42)") (class "Default")
      (node (ref "U3") (pin "42") (pinfunction "PA9_42") (pintype "bidirectional"))
    )
    (net (code "81") (name "unconnected-(U3-PA10-Pad43)") (class "Default")
      (node (ref "U3") (pin "43") (pinfunction "PA10_43") (pintype "bidirectional"))
    )
    (net (code "82") (name "unconnected-(U3-PA11-Pad44)") (class "Default")
      (node (ref "U3") (pin "44") (pinfunction "PA11_44") (pintype "bidirectional"))
    )
    (net (code "83") (name "unconnected-(U3-PA12-Pad45)") (class "Default")
      (node (ref "U3") (pin "45") (pinfunction "PA12_45") (pintype "bidirectional"))
    )
    (net (code "84") (name "unconnected-(U3-PA15-Pad50)") (class "Default")
      (node (ref "U3") (pin "50") (pinfunction "PA15_50") (pintype "bidirectional"))
    )
    (net (code "85") (name "unconnected-(U3-PB0-Pad26)") (class "Default")
      (node (ref "U3") (pin "26") (pinfunction "PB0_26") (pintype "bidirectional"))
    )
    (net (code "86") (name "unconnected-(U3-PB1-Pad27)") (class "Default")
      (node (ref "U3") (pin "27") (pinfunction "PB1_27") (pintype "bidirectional"))
    )
    (net (code "87") (name "unconnected-(U3-PB2-Pad28)") (class "Default")
      (node (ref "U3") (pin "28") (pinfunction "PB2_28") (pintype "bidirectional"))
    )
    (net (code "88") (name "unconnected-(U3-PB4-Pad56)") (class "Default")
      (node (ref "U3") (pin "56") (pinfunction "PB4_56") (pintype "bidirectional"))
    )
    (net (code "89") (name "unconnected-(U3-PB5-Pad57)") (class "Default")
      (node (ref "U3") (pin "57") (pinfunction "PB5_57") (pintype "bidirectional"))
    )
    (net (code "90") (name "unconnected-(U3-PB6-Pad58)") (class "Default")
      (node (ref "U3") (pin "58") (pinfunction "PB6_58") (pintype "bidirectional"))
    )
    (net (code "91") (name "unconnected-(U3-PB7-Pad59)") (class "Default")
      (node (ref "U3") (pin "59") (pinfunction "PB7_59") (pintype "bidirectional"))
    )
    (net (code "92") (name "unconnected-(U3-PB8-Pad61)") (class "Default")
      (node (ref "U3") (pin "61") (pinfunction "PB8_61") (pintype "bidirectional"))
    )
    (net (code "93") (name "unconnected-(U3-PB9-Pad62)") (class "Default")
      (node (ref "U3") (pin "62") (pinfunction "PB9_62") (pintype "bidirectional"))
    )
    (net (code "94") (name "unconnected-(U3-PB11-Pad30)") (class "Default")
      (node (ref "U3") (pin "30") (pinfunction "PB11_30") (pintype "bidirectional"))
    )
    (net (code "95") (name "unconnected-(U3-PC0-Pad8)") (class "Default")
      (node (ref "U3") (pin "8") (pinfunction "PC0_8") (pintype "bidirectional"))
    )
    (net (code "96") (name "unconnected-(U3-PC1-Pad9)") (class "Default")
      (node (ref "U3") (pin "9") (pinfunction "PC1_9") (pintype "bidirectional"))
    )
    (net (code "97") (name "unconnected-(U3-PC2-Pad10)") (class "Default")
      (node (ref "U3") (pin "10") (pinfunction "PC2_10") (pintype "bidirectional"))
    )
    (net (code "98") (name "unconnected-(U3-PC3-Pad11)") (class "Default")
      (node (ref "U3") (pin "11") (pinfunction "PC3_11") (pintype "bidirectional"))
    )
    (net (code "99") (name "unconnected-(U3-PC6-Pad37)") (class "Default")
      (node (ref "U3") (pin "37") (pinfunction "PC6_37") (pintype "bidirectional"))
    )
    (net (code "100") (name "unconnected-(U3-PC7-Pad38)") (class "Default")
      (node (ref "U3") (pin "38") (pinfunction "PC7_38") (pintype "bidirectional"))
    )
    (net (code "101") (name "unconnected-(U3-PC8-Pad39)") (class "Default")
      (node (ref "U3") (pin "39") (pinfunction "PC8_39") (pintype "bidirectional"))
    )
    (net (code "102") (name "unconnected-(U3-PC9-Pad40)") (class "Default")
      (node (ref "U3") (pin "40") (pinfunction "PC9_40") (pintype "bidirectional"))
    )
    (net (code "103") (name "unconnected-(U3-PC10-Pad51)") (class "Default")
      (node (ref "U3") (pin "51") (pinfunction "PC10_51") (pintype "bidirectional"))
    )
    (net (code "104") (name "unconnected-(U3-PC11-Pad52)") (class "Default")
      (node (ref "U3") (pin "52") (pinfunction "PC11_52") (pintype "bidirectional"))
    )
    (net (code "105") (name "unconnected-(U3-PC12-Pad53)") (class "Default")
      (node (ref "U3") (pin "53") (pinfunction "PC12_53") (pintype "bidirectional"))
    )
    (net (code "106") (name "unconnected-(U3-PC13-Pad2)") (class "Default")
      (node (ref "U3") (pin "2") (pinfunction "PC13_2") (pintype "bidirectional"))
    )
    (net (code "107") (name "unconnected-(U3-PC14-OSC32_IN-Pad3)") (class "Default")
      (node (ref "U3") (pin "3") (pinfunction "PC14-OSC32_IN_3") (pintype "bidirectional"))
    )
    (net (code "108") (name "unconnected-(U3-PC15-OSC32_OUT-Pad4)") (class "Default")
      (node (ref "U3") (pin "4") (pinfunction "PC15-OSC32_OUT_4") (pintype "bidirectional"))
    )
    (net (code "109") (name "unconnected-(U3-PD2-Pad54)") (class "Default")
      (node (ref "U3") (pin "54") (pinfunction "PD2_54") (pintype "bidirectional"))
    )
    (net (code "110") (name "unconnected-(U3-PF4-Pad18)") (class "Default")
      (node (ref "U3") (pin "18") (pinfunction "PF4_18") (pintype "bidirectional"))
    )
    (net (code "111") (name "unconnected-(U3-PF5-Pad19)") (class "Default")
      (node (ref "U3") (pin "19") (pinfunction "PF5_19") (pintype "bidirectional"))
    )
    (net (code "112") (name "unconnected-(U3-PF6-Pad47)") (class "Default")
      (node (ref "U3") (pin "47") (pinfunction "PF6_47") (pintype "bidirectional"))
    )
    (net (code "113") (name "unconnected-(U3-PF7-Pad48)") (class "Default")
      (node (ref "U3") (pin "48") (pinfunction "PF7_48") (pintype "bidirectional"))
    )
    (net (code "114") (name "unconnected-(XP2-Pad9)") (class "Default")
      (node (ref "XP2") (pin "9") (pinfunction "9_9") (pintype "passive"))
    )
    (net (code "115") (name "unconnected-(XP2-Pad10)") (class "Default")
      (node (ref "XP2") (pin "10") (pinfunction "10_10") (pintype "passive"))
    )
    (net (code "116") (name "unconnected-(XP2-Pad11)") (class "Default")
      (node (ref "XP2") (pin "11") (pinfunction "11_11") (pintype "passive"))
    )
    (net (code "117") (name "unconnected-(XP2-Pad12)") (class "Default")
      (node (ref "XP2") (pin "12") (pinfunction "12_12") (pintype "passive"))
    )
    (net (code "118") (name "unconnected-(XP2-Pad13)") (class "Default")
      (node (ref "XP2") (pin "13") (pinfunction "13_13") (pintype "passive"))
    )
    (net (code "119") (name "unconnected-(XP2-Pad14)") (class "Default")
      (node (ref "XP2") (pin "14") (pinfunction "14_14") (pintype "passive"))
    )
    (net (code "120") (name "unconnected-(XP2-Pad15)") (class "Default")
      (node (ref "XP2") (pin "15") (pinfunction "15_15") (pintype "passive"))
    )
    (net (code "121") (name "unconnected-(XP2-Pad16)") (class "Default")
      (node (ref "XP2") (pin "16") (pinfunction "16_16") (pintype "passive"))
    )
  )
)
